# L6924D013TR.net
KiCad netlist of a schematic drawn in Altium Designer
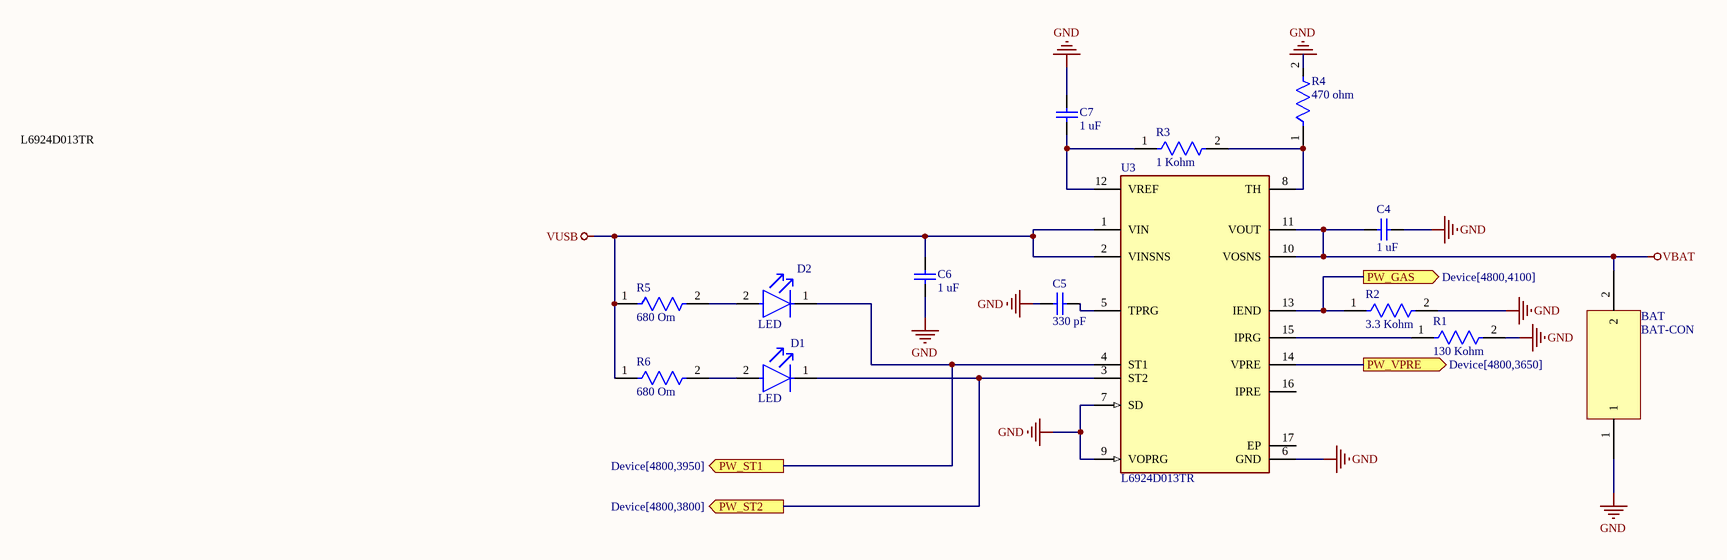
[diagram p0: L6924D013TR.SchDoc]

(export (version "E")
  (design (tool "Eeschema 10.0.6"))
  (components
    (comp (ref "BAT") (value "BAT-CON") (footprint "BAT-CON") (libsource (lib "Custom.") (part "BAT-CON")))
    (comp (ref "C4")
      (value "1 uF")
      (footprint "CAPC1005X55X25NL05T10")
      (fields (field (name "MANUFACTURER") "Murata") (field (name "PART NUMBER") "GRM155F50J684ZE01D"))
      (libsource (lib "Altium Content Vault") (part "CAP"))
    )
    (comp (ref "C5")
      (value "330 pF")
      (footprint "CAPC1005X55X25NL05T10")
      (fields (field (name "MANUFACTURER") "Murata") (field (name "PART NUMBER") "GRM155F50J684ZE01D"))
      (libsource (lib "Altium Content Vault") (part "CAP"))
    )
    (comp (ref "C6")
      (value "1 uF")
      (footprint "CAPC1005X55X25NL05T10")
      (fields (field (name "MANUFACTURER") "Murata") (field (name "PART NUMBER") "GRM155F50J684ZE01D"))
      (libsource (lib "Altium Content Vault") (part "CAP"))
    )
    (comp (ref "C7")
      (value "1 uF")
      (footprint "CAPC1005X55X25NL05T10")
      (fields (field (name "MANUFACTURER") "Murata") (field (name "PART NUMBER") "GRM155F50J684ZE01D"))
      (libsource (lib "Altium Content Vault") (part "CAP"))
    )
    (comp (ref "D1")
      (value "LED")
      (footprint "FP-SML-P11MTT86-MFG")
      (description "LED YELLOW/GREEN CLEAR 1006 SMD")
      (libsource (lib "Altium Content Vault") (part "8706943c75ba83719d021d2fdc84c58"))
    )
    (comp (ref "D2")
      (value "LED")
      (footprint "FP-SML-P11MTT86-MFG")
      (description "LED YELLOW/GREEN CLEAR 1006 SMD")
      (libsource (lib "Altium Content Vault") (part "8706943c75ba83719d021d2fdc84c58"))
    )
    (comp (ref "R1")
      (value "130 Kohm")
      (footprint "FP-RC1005-IPC_C")
      (description "Res Thick Film 0402 1.87kΩ 1% 0.063W ±100ppm/°C Molded SMD T/R")
      (fields (field (name "TOLERANCE") "1%"))
      (libsource (lib "Altium Content Vault") (part "1029c3af85768c4190bb7ad29bc67b5"))
    )
    (comp (ref "R2")
      (value "3.3 Kohm")
      (footprint "FP-RC1005-IPC_C")
      (description "Res Thick Film 0402 1.87kΩ 1% 0.063W ±100ppm/°C Molded SMD T/R")
      (fields (field (name "TOLERANCE") "1%"))
      (libsource (lib "Altium Content Vault") (part "1029c3af85768c4190bb7ad29bc67b5"))
    )
    (comp (ref "R3")
      (value "1 Kohm")
      (footprint "FP-RC1005-IPC_C")
      (description "Res Thick Film 0402 1.87kΩ 1% 0.063W ±100ppm/°C Molded SMD T/R")
      (fields (field (name "TOLERANCE") "1%"))
      (libsource (lib "Altium Content Vault") (part "1029c3af85768c4190bb7ad29bc67b5"))
    )
    (comp (ref "R4")
      (value "470 ohm")
      (footprint "FP-RC1005-IPC_C")
      (description "Res Thick Film 0402 1.87kΩ 1% 0.063W ±100ppm/°C Molded SMD T/R")
      (fields (field (name "TOLERANCE") "1%"))
      (libsource (lib "Altium Content Vault") (part "1029c3af85768c4190bb7ad29bc67b5"))
    )
    (comp (ref "R5")
      (value "680 Om")
      (footprint "FP-RC1005-IPC_C")
      (description "Res Thick Film 0402 1.87kΩ 1% 0.063W ±100ppm/°C Molded SMD T/R")
      (fields (field (name "TOLERANCE") "1%"))
      (libsource (lib "Altium Content Vault") (part "1029c3af85768c4190bb7ad29bc67b5"))
    )
    (comp (ref "R6")
      (value "680 Om")
      (footprint "FP-RC1005-IPC_C")
      (description "Res Thick Film 0402 1.87kΩ 1% 0.063W ±100ppm/°C Molded SMD T/R")
      (fields (field (name "TOLERANCE") "1%"))
      (libsource (lib "Altium Content Vault") (part "1029c3af85768c4190bb7ad29bc67b5"))
    )
    (comp (ref "U3")
      (value "L6924D013TR")
      (footprint "FP-VFQFPN16-7185330-MFG")
      (description "IC BATT CHRGR ION/POLY 16-VFQFPN")
      (fields
        (field (name "MANUFACTURER") "STMicroelectronics")
        (field (name "OCTOPART") "https://octopart.com/l6924d013tr-stmicroelectronics-421996")
      )
      (libsource (lib "Altium Content Vault") (part "9d43d87a5afbec7d73754d684d84cb7"))
    )
  )
  (nets
    (net (code "1") (name "/PW_GAS") (class "Default")
      (node (ref "R2") (pin "1") (pinfunction "1_1") (pintype "passive"))
      (node (ref "U3") (pin "13") (pinfunction "IEND_13") (pintype "passive"))
    )
    (net (code "2") (name "/PW_ST1") (class "Default")
      (node (ref "D2") (pin "1") (pinfunction "C_1") (pintype "passive"))
      (node (ref "U3") (pin "4") (pinfunction "ST1_4") (pintype "open_collector"))
    )
    (net (code "3") (name "/PW_ST2") (class "Default")
      (node (ref "D1") (pin "1") (pinfunction "C_1") (pintype "passive"))
      (node (ref "U3") (pin "3") (pinfunction "ST2_3") (pintype "open_collector"))
    )
    (net (code "4") (name "/PW_VPRE") (class "Default")
      (node (ref "U3") (pin "14") (pinfunction "VPRE_14") (pintype "passive"))
    )
    (net (code "5") (name "GND") (class "Default")
      (node (ref "BAT") (pin "1") (pinfunction "1_1") (pintype "power_in"))
      (node (ref "C4") (pin "1") (pinfunction "1_1") (pintype "passive"))
      (node (ref "C5") (pin "2") (pinfunction "2_2") (pintype "passive"))
      (node (ref "C6") (pin "2") (pinfunction "2_2") (pintype "passive"))
      (node (ref "C7") (pin "1") (pinfunction "1_1") (pintype "passive"))
      (node (ref "R1") (pin "2") (pinfunction "2_2") (pintype "passive"))
      (node (ref "R2") (pin "2") (pinfunction "2_2") (pintype "passive"))
      (node (ref "R4") (pin "2") (pinfunction "2_2") (pintype "passive"))
      (node (ref "U3") (pin "6") (pinfunction "GND_6") (pintype "power_in"))
      (node (ref "U3") (pin "7") (pinfunction "SD_7") (pintype "input"))
      (node (ref "U3") (pin "9") (pinfunction "VOPRG_9") (pintype "input"))
    )
    (net (code "6") (name "Net-(D1-A)") (class "Default")
      (node (ref "D1") (pin "2") (pinfunction "A_2") (pintype "passive"))
      (node (ref "R6") (pin "2") (pinfunction "2_2") (pintype "passive"))
    )
    (net (code "7") (name "Net-(D2-A)") (class "Default")
      (node (ref "D2") (pin "2") (pinfunction "A_2") (pintype "passive"))
      (node (ref "R5") (pin "2") (pinfunction "2_2") (pintype "passive"))
    )
    (net (code "8") (name "Net-(U3-IPRG)") (class "Default")
      (node (ref "R1") (pin "1") (pinfunction "1_1") (pintype "passive"))
      (node (ref "U3") (pin "15") (pinfunction "IPRG_15") (pintype "passive"))
    )
    (net (code "9") (name "Net-(U3-TH)") (class "Default")
      (node (ref "R3") (pin "2") (pinfunction "2_2") (pintype "passive"))
      (node (ref "R4") (pin "1") (pinfunction "1_1") (pintype "passive"))
      (node (ref "U3") (pin "8") (pinfunction "TH_8") (pintype "passive"))
    )
    (net (code "10") (name "Net-(U3-TPRG)") (class "Default")
      (node (ref "C5") (pin "1") (pinfunction "1_1") (pintype "passive"))
      (node (ref "U3") (pin "5") (pinfunction "TPRG_5") (pintype "passive"))
    )
    (net (code "11") (name "Net-(U3-VREF)") (class "Default")
      (node (ref "C7") (pin "2") (pinfunction "2_2") (pintype "passive"))
      (node (ref "R3") (pin "1") (pinfunction "1_1") (pintype "passive"))
      (node (ref "U3") (pin "12") (pinfunction "VREF_12") (pintype "power_in"))
    )
    (net (code "12") (name "VBAT") (class "Default")
      (node (ref "BAT") (pin "2") (pinfunction "2_2") (pintype "power_in"))
      (node (ref "C4") (pin "2") (pinfunction "2_2") (pintype "passive"))
      (node (ref "U3") (pin "10") (pinfunction "VOSNS_10") (pintype "passive"))
      (node (ref "U3") (pin "11") (pinfunction "VOUT_11") (pintype "power_in"))
    )
    (net (code "13") (name "VUSB") (class "Default")
      (node (ref "C6") (pin "1") (pinfunction "1_1") (pintype "passive"))
      (node (ref "R5") (pin "1") (pinfunction "1_1") (pintype "passive"))
      (node (ref "R6") (pin "1") (pinfunction "1_1") (pintype "passive"))
      (node (ref "U3") (pin "1") (pinfunction "VIN_1") (pintype "power_in"))
      (node (ref "U3") (pin "2") (pinfunction "VINSNS_2") (pintype "power_in"))
    )
    (net (code "14") (name "unconnected-(U3-EP-Pad17)") (class "Default")
      (node (ref "U3") (pin "17") (pinfunction "EP_17") (pintype "power_in"))
    )
    (net (code "15") (name "unconnected-(U3-IPRE-Pad16)") (class "Default")
      (node (ref "U3") (pin "16") (pinfunction "IPRE_16") (pintype "passive"))
    )
  )
)
